# Programmer_Card.net
KiCad netlist of a schematic drawn in EAGLE
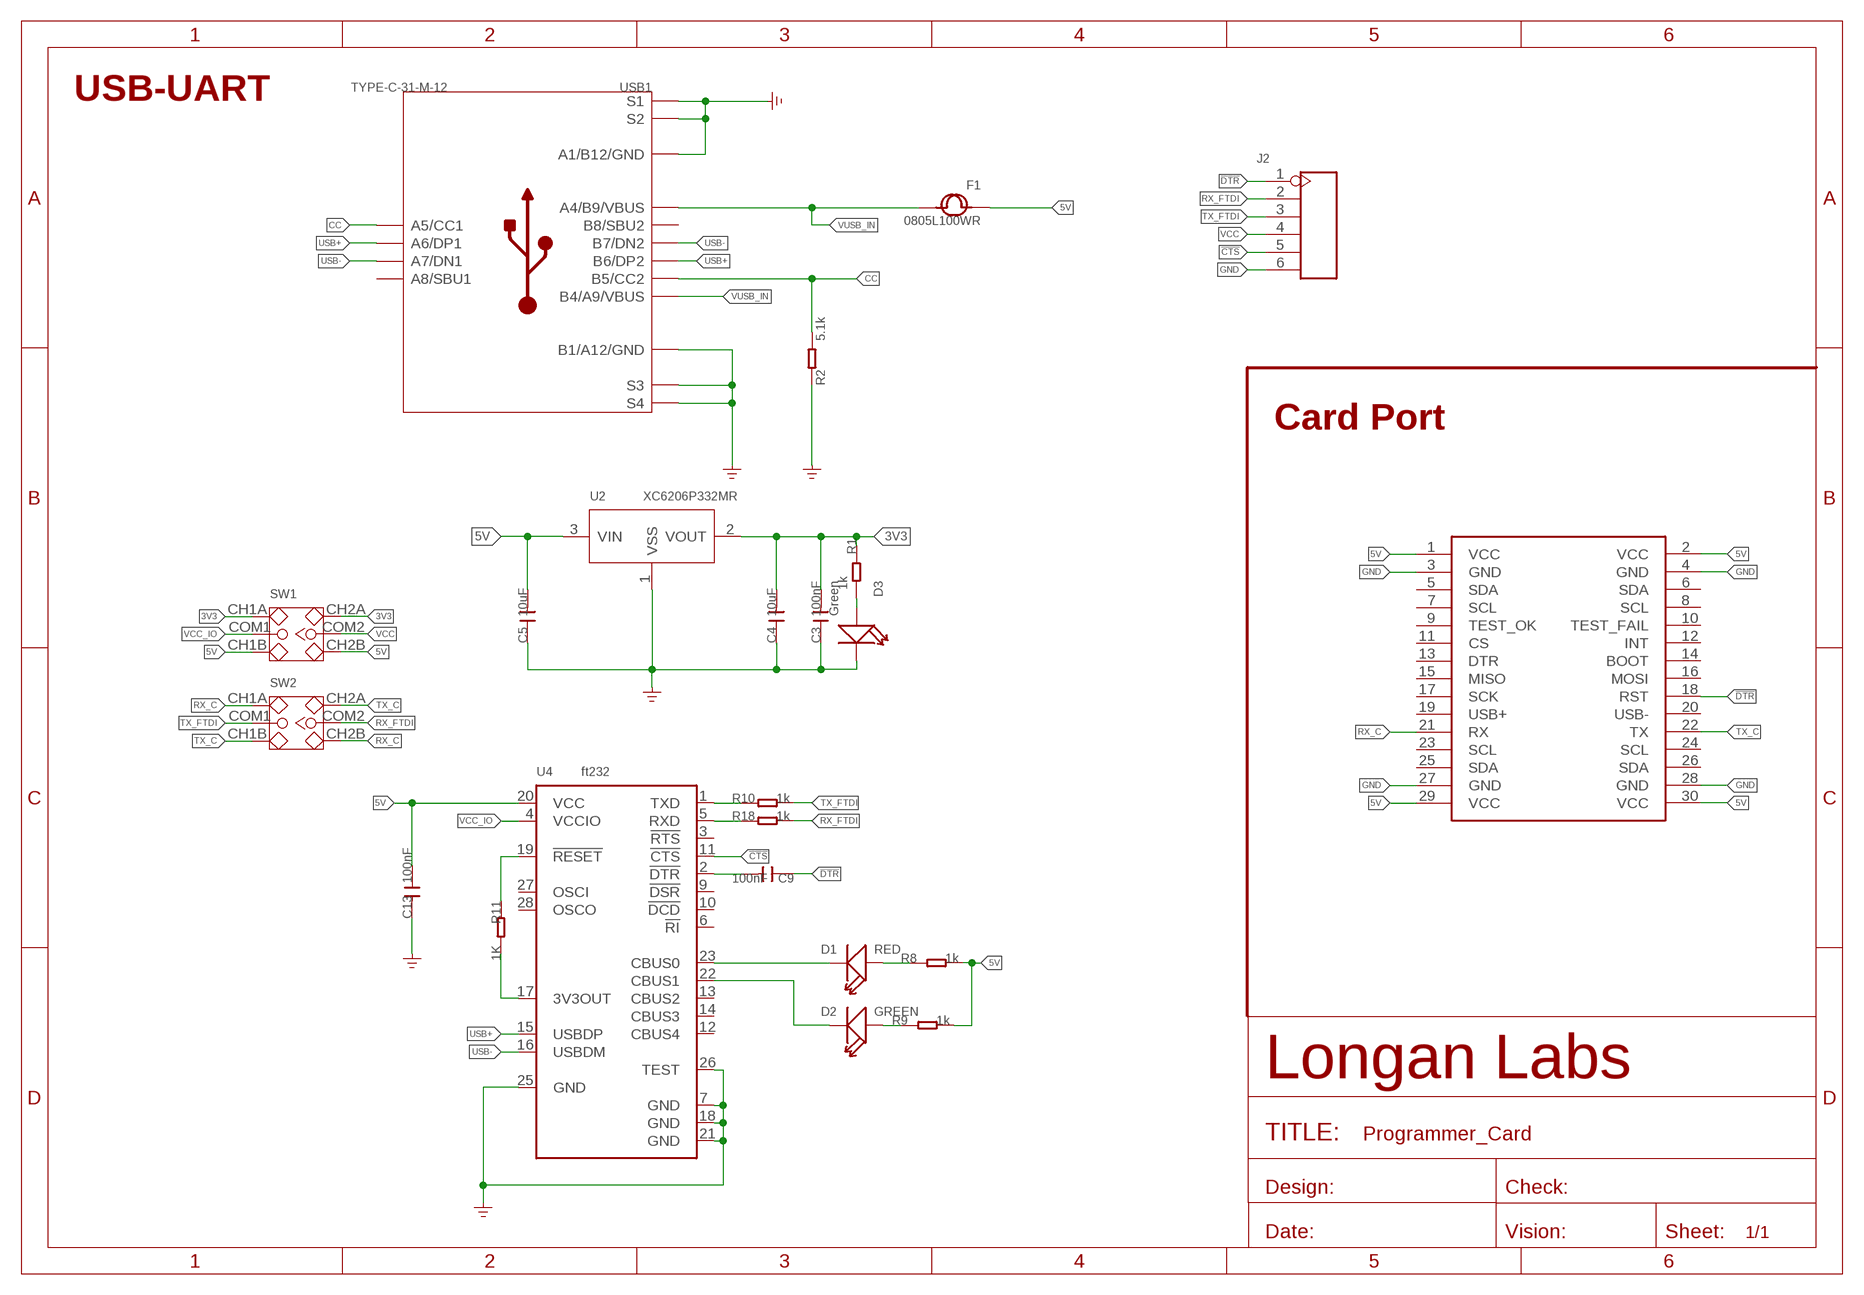
[diagram p0: schematic, sheet 1]

(export (version "E")
  (design (tool "Eeschema 10.0.6"))
  (components
    (comp (ref "C3")
      (value "100nF")
      (footprint "eagle-import:C0603")
      (libsource (lib "eagle-import") (part "C-0603"))
    )
    (comp (ref "C4")
      (value "10uF")
      (footprint "eagle-import:C0603")
      (libsource (lib "eagle-import") (part "C-0603"))
    )
    (comp (ref "C5")
      (value "10uF")
      (footprint "eagle-import:C0603")
      (libsource (lib "eagle-import") (part "C-0603"))
    )
    (comp (ref "C9")
      (value "100nF")
      (footprint "eagle-import:C0603")
      (libsource (lib "eagle-import") (part "C-0603"))
    )
    (comp (ref "C13")
      (value "100nF")
      (footprint "eagle-import:C0603")
      (libsource (lib "eagle-import") (part "CAP-0603"))
    )
    (comp (ref "D1")
      (value "RED")
      (footprint "eagle-import:LED-0603")
      (libsource (lib "eagle-import") (part "LED'0603'"))
    )
    (comp (ref "D2")
      (value "GREEN")
      (footprint "eagle-import:LED-0603")
      (libsource (lib "eagle-import") (part "LED'0603'"))
    )
    (comp (ref "D3")
      (value "Green")
      (footprint "eagle-import:LED-0603")
      (libsource (lib "eagle-import") (part "LED'0603'"))
    )
    (comp (ref "F1")
      (value "0805L100WR")
      (footprint "eagle-import:F0805")
      (libsource (lib "eagle-import") (part "FUSE0805"))
    )
    (comp (ref "J2")
      (value "HEADER-6P-65/35MIL")
      (footprint "eagle-import:H6-2.54-C65D35MIL")
      (libsource (lib "eagle-import") (part "HEADER-6P-65/35MIL"))
    )
    (comp (ref "MOUDLE1")
      (value "MOUDLE-2X15P-2.54'BOARD'")
      (footprint "eagle-import:MOUDLE-2X15P-2.54")
      (libsource (lib "eagle-import") (part "MOUDLE-2X15P-2.54'BOARD'"))
    )
    (comp (ref "R1")
      (value "1k")
      (footprint "eagle-import:R0603")
      (libsource (lib "eagle-import") (part "RES-0603"))
    )
    (comp (ref "R2")
      (value "5.1k")
      (footprint "eagle-import:R0603")
      (libsource (lib "eagle-import") (part "RES-0603"))
    )
    (comp (ref "R8")
      (value "1k")
      (footprint "eagle-import:R0603")
      (libsource (lib "eagle-import") (part "RES-0603"))
    )
    (comp (ref "R9")
      (value "1k")
      (footprint "eagle-import:R0603")
      (libsource (lib "eagle-import") (part "RES-0603"))
    )
    (comp (ref "R10")
      (value "1k")
      (footprint "eagle-import:R0603")
      (libsource (lib "eagle-import") (part "RES-0603"))
    )
    (comp (ref "R11")
      (value "1K")
      (footprint "eagle-import:R0603")
      (libsource (lib "eagle-import") (part "R-0603"))
    )
    (comp (ref "R18")
      (value "1k")
      (footprint "eagle-import:R0603")
      (libsource (lib "eagle-import") (part "RES-0603"))
    )
    (comp (ref "SW1")
      (value "SWITCH-2CH-6P")
      (footprint "eagle-import:SW6-2.5-SMD-9.2X3.5X3.5MM")
      (libsource (lib "eagle-import") (part "SWITCH-2CH-6P"))
    )
    (comp (ref "SW2")
      (value "SWITCH-2CH-6P")
      (footprint "eagle-import:SW6-2.5-SMD-9.2X3.5X3.5MM")
      (libsource (lib "eagle-import") (part "SWITCH-2CH-6P"))
    )
    (comp (ref "U2")
      (value "XC6206P332MR")
      (footprint "eagle-import:SOT-23")
      (libsource (lib "eagle-import") (part "PMIC-XC6206PMR"))
    )
    (comp (ref "U4")
      (value "ft232")
      (footprint "eagle-import:SSOP28-0.65-10.2X5.2MM")
      (libsource (lib "eagle-import") (part "INTERFACE-FT232RL-SSOP28"))
    )
    (comp (ref "USB1")
      (value "TYPE-C-31-M-12")
      (footprint "eagle-import:USB2.0-TYPE-C")
      (libsource (lib "eagle-import") (part "USB2.0-TYPE-C"))
    )
  )
  (nets
    (net (code "1") (name "/~{CTS}") (class "Default")
      (node (ref "J2") (pin "5") (pinfunction "5_5") (pintype "bidirectional"))
      (node (ref "U4") (pin "11") (pinfunction "~{CTS}_11") (pintype "input"))
    )
    (net (code "2") (name "/~{DTR}") (class "Default")
      (node (ref "C9") (pin "1") (pinfunction "1_1") (pintype "passive"))
      (node (ref "J2") (pin "1") (pinfunction "1_1") (pintype "bidirectional"))
      (node (ref "MOUDLE1") (pin "18") (pinfunction "RST_18") (pintype "bidirectional"))
    )
    (net (code "3") (name "3V3") (class "Default")
      (node (ref "C3") (pin "2") (pinfunction "2_2") (pintype "passive"))
      (node (ref "C4") (pin "2") (pinfunction "2_2") (pintype "passive"))
      (node (ref "R1") (pin "1") (pinfunction "1_1") (pintype "passive"))
      (node (ref "SW1") (pin "CH1A") (pinfunction "CH1A_CH1A") (pintype "bidirectional"))
      (node (ref "SW1") (pin "CH2A") (pinfunction "CH2A_CH2A") (pintype "bidirectional"))
      (node (ref "U2") (pin "2") (pinfunction "VOUT_2") (pintype "bidirectional"))
    )
    (net (code "4") (name "5V") (class "Default")
      (node (ref "C13") (pin "1") (pinfunction "1_1") (pintype "passive"))
      (node (ref "C5") (pin "2") (pinfunction "2_2") (pintype "passive"))
      (node (ref "F1") (pin "1") (pinfunction "1_1") (pintype "bidirectional"))
      (node (ref "MOUDLE1") (pin "1") (pinfunction "VCC_1") (pintype "bidirectional"))
      (node (ref "MOUDLE1") (pin "2") (pinfunction "VCC_2") (pintype "bidirectional"))
      (node (ref "MOUDLE1") (pin "29") (pinfunction "VCC_29") (pintype "bidirectional"))
      (node (ref "MOUDLE1") (pin "30") (pinfunction "VCC_30") (pintype "bidirectional"))
      (node (ref "R8") (pin "2") (pinfunction "2_2") (pintype "passive"))
      (node (ref "R9") (pin "2") (pinfunction "2_2") (pintype "passive"))
      (node (ref "SW1") (pin "CH1B") (pinfunction "CH1B_CH1B") (pintype "bidirectional"))
      (node (ref "SW1") (pin "CH2B") (pinfunction "CH2B_CH2B") (pintype "bidirectional"))
      (node (ref "U2") (pin "3") (pinfunction "VIN_3") (pintype "bidirectional"))
      (node (ref "U4") (pin "20") (pinfunction "VCC_20") (pintype "input"))
    )
    (net (code "5") (name "CC") (class "Default")
      (node (ref "R2") (pin "2") (pinfunction "2_2") (pintype "passive"))
      (node (ref "USB1") (pin "A5") (pinfunction "A5/CC1_A5") (pintype "bidirectional"))
      (node (ref "USB1") (pin "B5") (pinfunction "B5/CC2_B5") (pintype "bidirectional"))
    )
    (net (code "6") (name "GND") (class "Default")
      (node (ref "C13") (pin "2") (pinfunction "2_2") (pintype "passive"))
      (node (ref "C3") (pin "1") (pinfunction "1_1") (pintype "passive"))
      (node (ref "C4") (pin "1") (pinfunction "1_1") (pintype "passive"))
      (node (ref "C5") (pin "1") (pinfunction "1_1") (pintype "passive"))
      (node (ref "D3") (pin "-") (pinfunction "-_-") (pintype "passive"))
      (node (ref "J2") (pin "6") (pinfunction "6_6") (pintype "bidirectional"))
      (node (ref "MOUDLE1") (pin "27") (pinfunction "GND_27") (pintype "bidirectional"))
      (node (ref "MOUDLE1") (pin "28") (pinfunction "GND_28") (pintype "bidirectional"))
      (node (ref "MOUDLE1") (pin "3") (pinfunction "GND_3") (pintype "bidirectional"))
      (node (ref "MOUDLE1") (pin "4") (pinfunction "GND_4") (pintype "bidirectional"))
      (node (ref "R2") (pin "1") (pinfunction "1_1") (pintype "passive"))
      (node (ref "U2") (pin "1") (pinfunction "VSS_1") (pintype "bidirectional"))
      (node (ref "U4") (pin "18") (pinfunction "GND_18") (pintype "input"))
      (node (ref "U4") (pin "21") (pinfunction "GND_21") (pintype "input"))
      (node (ref "U4") (pin "25") (pinfunction "GND_25") (pintype "input"))
      (node (ref "U4") (pin "26") (pinfunction "TEST_26") (pintype "input"))
      (node (ref "U4") (pin "7") (pinfunction "GND_7") (pintype "input"))
      (node (ref "USB1") (pin "A1_B12") (pinfunction "A1/B12/GND_A1_B12") (pintype "bidirectional"))
      (node (ref "USB1") (pin "B1_A12") (pinfunction "B1/A12/GND_B1_A12") (pintype "bidirectional"))
      (node (ref "USB1") (pin "S1") (pinfunction "S1_S1") (pintype "bidirectional"))
      (node (ref "USB1") (pin "S2") (pinfunction "S2_S2") (pintype "bidirectional"))
      (node (ref "USB1") (pin "S3") (pinfunction "S3_S3") (pintype "bidirectional"))
      (node (ref "USB1") (pin "S4") (pinfunction "S4_S4") (pintype "bidirectional"))
      (node (ref "USB1") (pin "S5") (pinfunction "S1_S5") (pintype "bidirectional"))
      (node (ref "USB1") (pin "S6") (pinfunction "S2_S6") (pintype "bidirectional"))
    )
    (net (code "7") (name "Net-(D1-Pad+)") (class "Default")
      (node (ref "D1") (pin "+") (pinfunction "+_+") (pintype "passive"))
      (node (ref "R8") (pin "1") (pinfunction "1_1") (pintype "passive"))
    )
    (net (code "8") (name "Net-(D2-Pad+)") (class "Default")
      (node (ref "D2") (pin "+") (pinfunction "+_+") (pintype "passive"))
      (node (ref "R9") (pin "1") (pinfunction "1_1") (pintype "passive"))
    )
    (net (code "9") (name "Net-(D3-Pad+)") (class "Default")
      (node (ref "D3") (pin "+") (pinfunction "+_+") (pintype "passive"))
      (node (ref "R1") (pin "2") (pinfunction "2_2") (pintype "passive"))
    )
    (net (code "10") (name "Net-(U4-3V3OUT)") (class "Default")
      (node (ref "R11") (pin "2") (pinfunction "2_2") (pintype "passive"))
      (node (ref "U4") (pin "17") (pinfunction "3V3OUT_17") (pintype "input"))
    )
    (net (code "11") (name "Net-(U4-CBUS0)") (class "Default")
      (node (ref "D1") (pin "-") (pinfunction "-_-") (pintype "passive"))
      (node (ref "U4") (pin "23") (pinfunction "CBUS0_23") (pintype "input"))
    )
    (net (code "12") (name "Net-(U4-CBUS1)") (class "Default")
      (node (ref "D2") (pin "-") (pinfunction "-_-") (pintype "passive"))
      (node (ref "U4") (pin "22") (pinfunction "CBUS1_22") (pintype "input"))
    )
    (net (code "13") (name "Net-(U4-RXD)") (class "Default")
      (node (ref "R18") (pin "1") (pinfunction "1_1") (pintype "passive"))
      (node (ref "U4") (pin "5") (pinfunction "RXD_5") (pintype "input"))
    )
    (net (code "14") (name "Net-(U4-TXD)") (class "Default")
      (node (ref "R10") (pin "1") (pinfunction "1_1") (pintype "passive"))
      (node (ref "U4") (pin "1") (pinfunction "TXD_1") (pintype "input"))
    )
    (net (code "15") (name "Net-(U4-~{DTR})") (class "Default")
      (node (ref "C9") (pin "2") (pinfunction "2_2") (pintype "passive"))
      (node (ref "U4") (pin "2") (pinfunction "~{DTR}_2") (pintype "input"))
    )
    (net (code "16") (name "Net-(U4-~{RESET})") (class "Default")
      (node (ref "R11") (pin "1") (pinfunction "1_1") (pintype "passive"))
      (node (ref "U4") (pin "19") (pinfunction "~{RESET}_19") (pintype "input"))
    )
    (net (code "17") (name "RX_C") (class "Default")
      (node (ref "MOUDLE1") (pin "21") (pinfunction "RX_21") (pintype "bidirectional"))
      (node (ref "SW2") (pin "CH1A") (pinfunction "CH1A_CH1A") (pintype "bidirectional"))
      (node (ref "SW2") (pin "CH2B") (pinfunction "CH2B_CH2B") (pintype "bidirectional"))
    )
    (net (code "18") (name "RX_FTDI") (class "Default")
      (node (ref "J2") (pin "2") (pinfunction "2_2") (pintype "bidirectional"))
      (node (ref "R18") (pin "2") (pinfunction "2_2") (pintype "passive"))
      (node (ref "SW2") (pin "COM2") (pinfunction "COM2_COM2") (pintype "bidirectional"))
    )
    (net (code "19") (name "TX_C") (class "Default")
      (node (ref "MOUDLE1") (pin "22") (pinfunction "TX_22") (pintype "bidirectional"))
      (node (ref "SW2") (pin "CH1B") (pinfunction "CH1B_CH1B") (pintype "bidirectional"))
      (node (ref "SW2") (pin "CH2A") (pinfunction "CH2A_CH2A") (pintype "bidirectional"))
    )
    (net (code "20") (name "TX_FTDI") (class "Default")
      (node (ref "J2") (pin "3") (pinfunction "3_3") (pintype "bidirectional"))
      (node (ref "R10") (pin "2") (pinfunction "2_2") (pintype "passive"))
      (node (ref "SW2") (pin "COM1") (pinfunction "COM1_COM1") (pintype "bidirectional"))
    )
    (net (code "21") (name "USB+") (class "Default")
      (node (ref "U4") (pin "15") (pinfunction "USBDP_15") (pintype "input"))
      (node (ref "USB1") (pin "A6") (pinfunction "A6/DP1_A6") (pintype "bidirectional"))
      (node (ref "USB1") (pin "B6") (pinfunction "B6/DP2_B6") (pintype "bidirectional"))
    )
    (net (code "22") (name "USB-") (class "Default")
      (node (ref "U4") (pin "16") (pinfunction "USBDM_16") (pintype "input"))
      (node (ref "USB1") (pin "A7") (pinfunction "A7/DN1_A7") (pintype "bidirectional"))
      (node (ref "USB1") (pin "B7") (pinfunction "B7/DN2_B7") (pintype "bidirectional"))
    )
    (net (code "23") (name "VCC") (class "Default")
      (node (ref "J2") (pin "4") (pinfunction "4_4") (pintype "bidirectional"))
      (node (ref "SW1") (pin "COM2") (pinfunction "COM2_COM2") (pintype "bidirectional"))
    )
    (net (code "24") (name "VCC_IO") (class "Default")
      (node (ref "SW1") (pin "COM1") (pinfunction "COM1_COM1") (pintype "bidirectional"))
      (node (ref "U4") (pin "4") (pinfunction "VCCIO_4") (pintype "input"))
    )
    (net (code "25") (name "VUSB_IN") (class "Default")
      (node (ref "F1") (pin "2") (pinfunction "2_2") (pintype "bidirectional"))
      (node (ref "USB1") (pin "A4_B9") (pinfunction "A4/B9/VBUS_A4_B9") (pintype "bidirectional"))
      (node (ref "USB1") (pin "B4_A9") (pinfunction "B4/A9/VBUS_B4_A9") (pintype "bidirectional"))
    )
    (net (code "26") (name "unconnected-(MOUDLE1-BOOT-Pad14)") (class "Default")
      (node (ref "MOUDLE1") (pin "14") (pinfunction "BOOT_14") (pintype "bidirectional"))
    )
    (net (code "27") (name "unconnected-(MOUDLE1-CS-Pad11)") (class "Default")
      (node (ref "MOUDLE1") (pin "11") (pinfunction "CS_11") (pintype "bidirectional"))
    )
    (net (code "28") (name "unconnected-(MOUDLE1-DTR-Pad13)") (class "Default")
      (node (ref "MOUDLE1") (pin "13") (pinfunction "DTR_13") (pintype "bidirectional"))
    )
    (net (code "29") (name "unconnected-(MOUDLE1-INT-Pad12)") (class "Default")
      (node (ref "MOUDLE1") (pin "12") (pinfunction "INT_12") (pintype "bidirectional"))
    )
    (net (code "30") (name "unconnected-(MOUDLE1-MISO-Pad15)") (class "Default")
      (node (ref "MOUDLE1") (pin "15") (pinfunction "MISO_15") (pintype "bidirectional"))
    )
    (net (code "31") (name "unconnected-(MOUDLE1-MOSI-Pad16)") (class "Default")
      (node (ref "MOUDLE1") (pin "16") (pinfunction "MOSI_16") (pintype "bidirectional"))
    )
    (net (code "32") (name "unconnected-(MOUDLE1-SCK-Pad17)") (class "Default")
      (node (ref "MOUDLE1") (pin "17") (pinfunction "SCK_17") (pintype "bidirectional"))
    )
    (net (code "33") (name "unconnected-(MOUDLE1-SCL-Pad7)") (class "Default")
      (node (ref "MOUDLE1") (pin "7") (pinfunction "SCL_7") (pintype "bidirectional"))
    )
    (net (code "34") (name "unconnected-(MOUDLE1-SCL-Pad8)") (class "Default")
      (node (ref "MOUDLE1") (pin "8") (pinfunction "SCL_8") (pintype "bidirectional"))
    )
    (net (code "35") (name "unconnected-(MOUDLE1-SCL-Pad23)") (class "Default")
      (node (ref "MOUDLE1") (pin "23") (pinfunction "SCL_23") (pintype "bidirectional"))
    )
    (net (code "36") (name "unconnected-(MOUDLE1-SCL-Pad24)") (class "Default")
      (node (ref "MOUDLE1") (pin "24") (pinfunction "SCL_24") (pintype "bidirectional"))
    )
    (net (code "37") (name "unconnected-(MOUDLE1-SDA-Pad5)") (class "Default")
      (node (ref "MOUDLE1") (pin "5") (pinfunction "SDA_5") (pintype "bidirectional"))
    )
    (net (code "38") (name "unconnected-(MOUDLE1-SDA-Pad6)") (class "Default")
      (node (ref "MOUDLE1") (pin "6") (pinfunction "SDA_6") (pintype "bidirectional"))
    )
    (net (code "39") (name "unconnected-(MOUDLE1-SDA-Pad25)") (class "Default")
      (node (ref "MOUDLE1") (pin "25") (pinfunction "SDA_25") (pintype "bidirectional"))
    )
    (net (code "40") (name "unconnected-(MOUDLE1-SDA-Pad26)") (class "Default")
      (node (ref "MOUDLE1") (pin "26") (pinfunction "SDA_26") (pintype "bidirectional"))
    )
    (net (code "41") (name "unconnected-(MOUDLE1-TEST_FAIL-Pad10)") (class "Default")
      (node (ref "MOUDLE1") (pin "10") (pinfunction "TEST_FAIL_10") (pintype "bidirectional"))
    )
    (net (code "42") (name "unconnected-(MOUDLE1-TEST_OK-Pad9)") (class "Default")
      (node (ref "MOUDLE1") (pin "9") (pinfunction "TEST_OK_9") (pintype "bidirectional"))
    )
    (net (code "43") (name "unconnected-(MOUDLE1-USB+-Pad19)") (class "Default")
      (node (ref "MOUDLE1") (pin "19") (pinfunction "USB+_19") (pintype "bidirectional"))
    )
    (net (code "44") (name "unconnected-(MOUDLE1-USB--Pad20)") (class "Default")
      (node (ref "MOUDLE1") (pin "20") (pinfunction "USB-_20") (pintype "bidirectional"))
    )
    (net (code "45") (name "unconnected-(U4-CBUS2-Pad13)") (class "Default")
      (node (ref "U4") (pin "13") (pinfunction "CBUS2_13") (pintype "input"))
    )
    (net (code "46") (name "unconnected-(U4-CBUS3-Pad14)") (class "Default")
      (node (ref "U4") (pin "14") (pinfunction "CBUS3_14") (pintype "input"))
    )
    (net (code "47") (name "unconnected-(U4-CBUS4-Pad12)") (class "Default")
      (node (ref "U4") (pin "12") (pinfunction "CBUS4_12") (pintype "input"))
    )
    (net (code "48") (name "unconnected-(U4-OSCI-Pad27)") (class "Default")
      (node (ref "U4") (pin "27") (pinfunction "OSCI_27") (pintype "input"))
    )
    (net (code "49") (name "unconnected-(U4-OSCO-Pad28)") (class "Default")
      (node (ref "U4") (pin "28") (pinfunction "OSCO_28") (pintype "input"))
    )
    (net (code "50") (name "unconnected-(U4-~{DCD}-Pad10)") (class "Default")
      (node (ref "U4") (pin "10") (pinfunction "~{DCD}_10") (pintype "input"))
    )
    (net (code "51") (name "unconnected-(U4-~{DSR}-Pad9)") (class "Default")
      (node (ref "U4") (pin "9") (pinfunction "~{DSR}_9") (pintype "input"))
    )
    (net (code "52") (name "unconnected-(U4-~{RI}-Pad6)") (class "Default")
      (node (ref "U4") (pin "6") (pinfunction "~{RI}_6") (pintype "input"))
    )
    (net (code "53") (name "unconnected-(U4-~{RTS}-Pad3)") (class "Default")
      (node (ref "U4") (pin "3") (pinfunction "~{RTS}_3") (pintype "input"))
    )
    (net (code "54") (name "unconnected-(USB1-A8{slash}SBU1-PadA8)") (class "Default")
      (node (ref "USB1") (pin "A8") (pinfunction "A8/SBU1_A8") (pintype "bidirectional"))
    )
    (net (code "55") (name "unconnected-(USB1-B8{slash}SBU2-PadB8)") (class "Default")
      (node (ref "USB1") (pin "B8") (pinfunction "B8/SBU2_B8") (pintype "bidirectional"))
    )
  )
)
